# BUS.net
KiCad netlist of a schematic drawn in Altium Designer
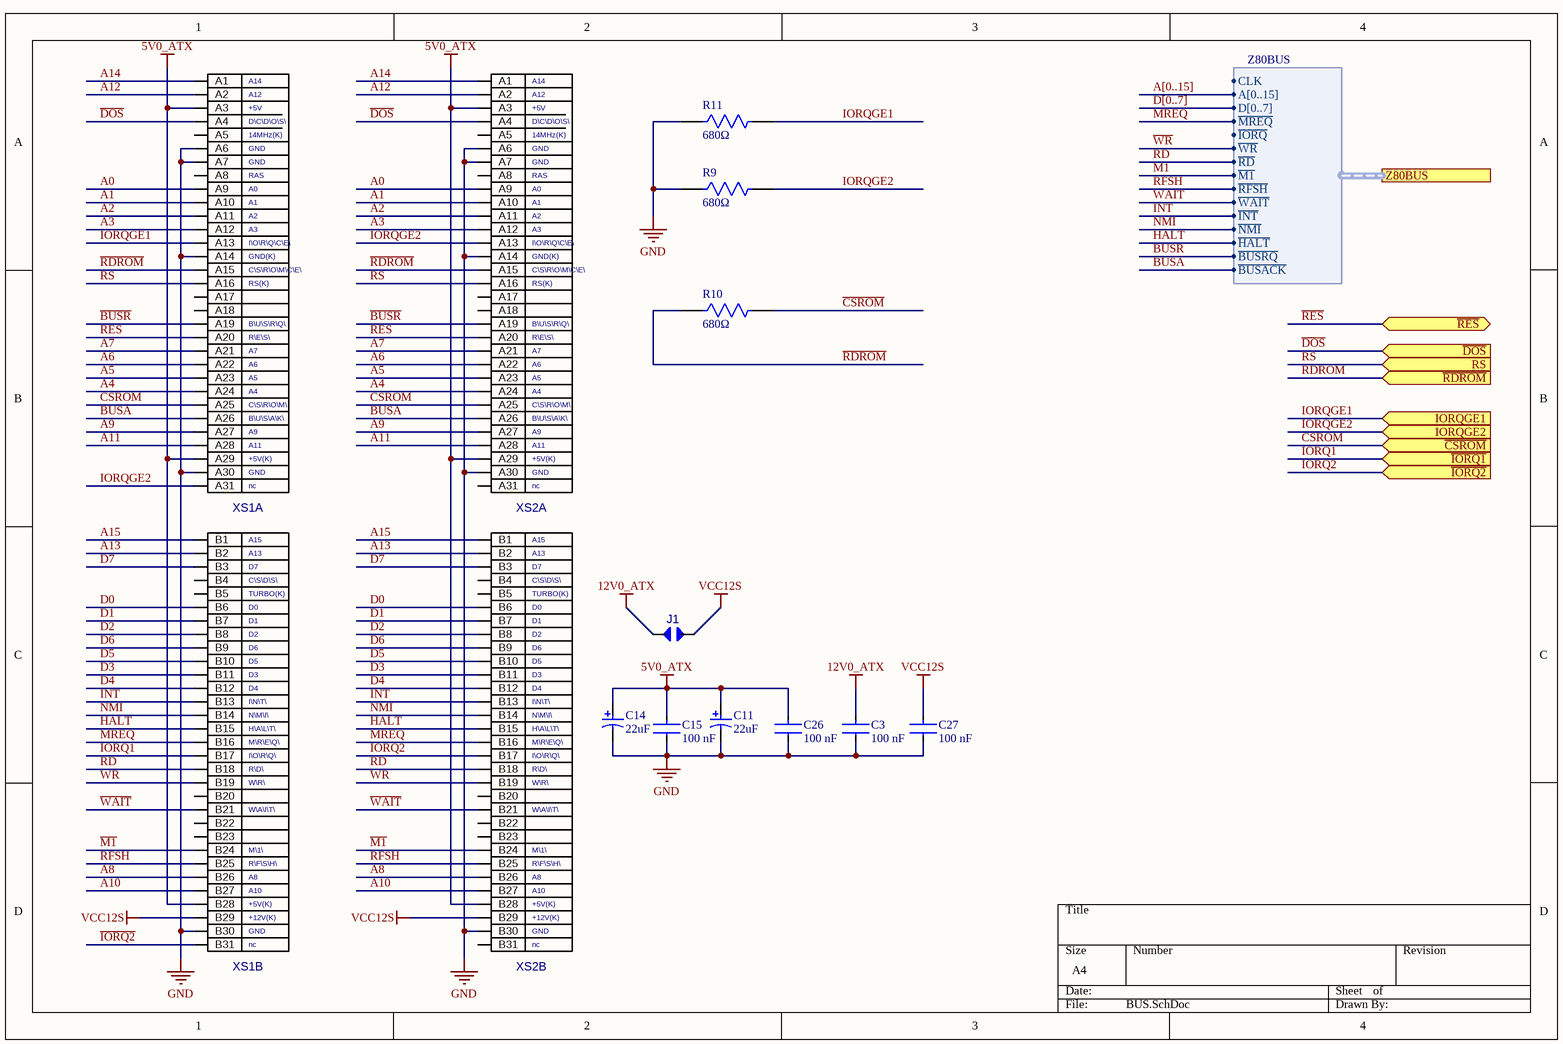
[diagram p0: BUS.SchDoc]

(export (version "E")
  (design (tool "Eeschema 10.0.6"))
  (components
    (comp (ref "C3")
      (value "CC0805KRX7R9BB104")
      (footprint "FP-CC0805-0_85-IPC_A")
      (description "CAP CER 0.1UF 50V X7R 0805")
      (fields (field (name "CAPACITANCE") "100 nF") (field (name "MANUFACTURER") "Yageo"))
      (libsource (lib "SchLib") (part "CMP-2100-03606-3"))
    )
    (comp (ref "C11")
      (value "TAJB226K016RNJ")
      (footprint "AVX-TAJ-B-2_M")
      (description "Standard Tantalum, 22 uF, +/- 10%, 16 V, -55 to 125 degC, 2-Pin SMD (1210), RoHS, Tape and Reel")
      (fields (field (name "CAPACITANCE") "22uF") (field (name "MANUFACTURER") "Kyocera AVX"))
      (libsource (lib "SchLib") (part "CMP-2100-03689-1"))
    )
    (comp (ref "C14")
      (value "TAJB226K016RNJ")
      (footprint "AVX-TAJ-B-2_M")
      (description "Standard Tantalum, 22 uF, +/- 10%, 16 V, -55 to 125 degC, 2-Pin SMD (1210), RoHS, Tape and Reel")
      (fields (field (name "CAPACITANCE") "22uF") (field (name "MANUFACTURER") "Kyocera AVX"))
      (libsource (lib "SchLib") (part "CMP-2100-03689-1"))
    )
    (comp (ref "C15")
      (value "CC0805KRX7R9BB104")
      (footprint "FP-CC0805-0_85-IPC_A")
      (description "CAP CER 0.1UF 50V X7R 0805")
      (fields (field (name "CAPACITANCE") "100 nF") (field (name "MANUFACTURER") "Yageo"))
      (libsource (lib "SchLib") (part "CMP-2100-03606-3"))
    )
    (comp (ref "C26")
      (value "CC0805KRX7R9BB104")
      (footprint "FP-CC0805-0_85-IPC_A")
      (description "CAP CER 0.1UF 50V X7R 0805")
      (fields (field (name "CAPACITANCE") "100 nF") (field (name "MANUFACTURER") "Yageo"))
      (libsource (lib "SchLib") (part "CMP-2100-03606-3"))
    )
    (comp (ref "C27")
      (value "CC0805KRX7R9BB104")
      (footprint "FP-CC0805-0_85-IPC_A")
      (description "CAP CER 0.1UF 50V X7R 0805")
      (fields (field (name "CAPACITANCE") "100 nF") (field (name "MANUFACTURER") "Yageo"))
      (libsource (lib "SchLib") (part "CMP-2100-03606-3"))
    )
    (comp (ref "J1")
      (value "JUMPER")
      (footprint "JUMPER_JUMPER(Primary)")
      (description "HLT->~IP")
      (libsource (lib "SchLib") (part "JUMPER"))
    )
    (comp (ref "R9")
      (value "680Ω")
      (footprint "FP-RT0805-IPC_A")
      (description "RES SMD 680 OHM 1% 1/8W 0805")
      (fields
        (field (name "MANUFACTURER") "Yageo")
        (field (name "MANUFACTURER PART NUMBER") "RT0805FRE07680RL")
      )
      (libsource (lib "SchLib") (part "CMP-03412-000082-1"))
    )
    (comp (ref "R10")
      (value "680Ω")
      (footprint "FP-RT0805-IPC_A")
      (description "RES SMD 680 OHM 1% 1/8W 0805")
      (fields
        (field (name "MANUFACTURER") "Yageo")
        (field (name "MANUFACTURER PART NUMBER") "RT0805FRE07680RL")
      )
      (libsource (lib "SchLib") (part "CMP-03412-000082-1"))
    )
    (comp (ref "R11")
      (value "680Ω")
      (footprint "FP-RT0805-IPC_A")
      (description "RES SMD 680 OHM 1% 1/8W 0805")
      (fields
        (field (name "MANUFACTURER") "Yageo")
        (field (name "MANUFACTURER PART NUMBER") "RT0805FRE07680RL")
      )
      (libsource (lib "SchLib") (part "CMP-03412-000082-1"))
    )
    (comp (ref "XS1")
      (value "ZXSLOT")
      (footprint "SLOT62_ZXSLOT(Primary)")
      (libsource (lib "SchLib") (part "ZXSLOT"))
    )
    (comp (ref "XS2")
      (value "ZXSLOT")
      (footprint "SLOT62_ZXSLOT(Primary)")
      (libsource (lib "SchLib") (part "ZXSLOT"))
    )
  )
  (nets
    (net (code "2") (name "/A0") (class "Default")
      (node (ref "XS1") (pin "A9") (pinfunction "A9_A9") (pintype "passive"))
      (node (ref "XS2") (pin "A9") (pinfunction "A9_A9") (pintype "passive"))
    )
    (net (code "3") (name "/A1") (class "Default")
      (node (ref "XS1") (pin "A10") (pinfunction "A10_A10") (pintype "passive"))
      (node (ref "XS2") (pin "A10") (pinfunction "A10_A10") (pintype "passive"))
    )
    (net (code "4") (name "/A2") (class "Default")
      (node (ref "XS1") (pin "A11") (pinfunction "A11_A11") (pintype "passive"))
      (node (ref "XS2") (pin "A11") (pinfunction "A11_A11") (pintype "passive"))
    )
    (net (code "5") (name "/A3") (class "Default")
      (node (ref "XS1") (pin "A12") (pinfunction "A12_A12") (pintype "passive"))
      (node (ref "XS2") (pin "A12") (pinfunction "A12_A12") (pintype "passive"))
    )
    (net (code "6") (name "/A4") (class "Default")
      (node (ref "XS1") (pin "A24") (pinfunction "A24_A24") (pintype "passive"))
      (node (ref "XS2") (pin "A24") (pinfunction "A24_A24") (pintype "passive"))
    )
    (net (code "7") (name "/A5") (class "Default")
      (node (ref "XS1") (pin "A23") (pinfunction "A23_A23") (pintype "passive"))
      (node (ref "XS2") (pin "A23") (pinfunction "A23_A23") (pintype "passive"))
    )
    (net (code "8") (name "/A6") (class "Default")
      (node (ref "XS1") (pin "A22") (pinfunction "A22_A22") (pintype "passive"))
      (node (ref "XS2") (pin "A22") (pinfunction "A22_A22") (pintype "passive"))
    )
    (net (code "9") (name "/A7") (class "Default")
      (node (ref "XS1") (pin "A21") (pinfunction "A21_A21") (pintype "passive"))
      (node (ref "XS2") (pin "A21") (pinfunction "A21_A21") (pintype "passive"))
    )
    (net (code "10") (name "/A8") (class "Default")
      (node (ref "XS1") (pin "B26") (pinfunction "B26_B26") (pintype "passive"))
      (node (ref "XS2") (pin "B26") (pinfunction "B26_B26") (pintype "passive"))
    )
    (net (code "11") (name "/A9") (class "Default")
      (node (ref "XS1") (pin "A27") (pinfunction "A27_A27") (pintype "passive"))
      (node (ref "XS2") (pin "A27") (pinfunction "A27_A27") (pintype "passive"))
    )
    (net (code "12") (name "/A10") (class "Default")
      (node (ref "XS1") (pin "B27") (pinfunction "B27_B27") (pintype "passive"))
      (node (ref "XS2") (pin "B27") (pinfunction "B27_B27") (pintype "passive"))
    )
    (net (code "13") (name "/A11") (class "Default")
      (node (ref "XS1") (pin "A28") (pinfunction "A28_A28") (pintype "passive"))
      (node (ref "XS2") (pin "A28") (pinfunction "A28_A28") (pintype "passive"))
    )
    (net (code "14") (name "/A12") (class "Default")
      (node (ref "XS1") (pin "A2") (pinfunction "A2_A2") (pintype "passive"))
      (node (ref "XS2") (pin "A2") (pinfunction "A2_A2") (pintype "passive"))
    )
    (net (code "15") (name "/A13") (class "Default")
      (node (ref "XS1") (pin "B2") (pinfunction "B2_B2") (pintype "passive"))
      (node (ref "XS2") (pin "B2") (pinfunction "B2_B2") (pintype "passive"))
    )
    (net (code "16") (name "/A14") (class "Default")
      (node (ref "XS1") (pin "A1") (pinfunction "A1_A1") (pintype "passive"))
      (node (ref "XS2") (pin "A1") (pinfunction "A1_A1") (pintype "passive"))
    )
    (net (code "17") (name "/A15") (class "Default")
      (node (ref "XS1") (pin "B1") (pinfunction "B1_B1") (pintype "passive"))
      (node (ref "XS2") (pin "B1") (pinfunction "B1_B1") (pintype "passive"))
    )
    (net (code "18") (name "/D0") (class "Default")
      (node (ref "XS1") (pin "B6") (pinfunction "B6_B6") (pintype "passive"))
      (node (ref "XS2") (pin "B6") (pinfunction "B6_B6") (pintype "passive"))
    )
    (net (code "19") (name "/D1") (class "Default")
      (node (ref "XS1") (pin "B7") (pinfunction "B7_B7") (pintype "passive"))
      (node (ref "XS2") (pin "B7") (pinfunction "B7_B7") (pintype "passive"))
    )
    (net (code "20") (name "/D2") (class "Default")
      (node (ref "XS1") (pin "B8") (pinfunction "B8_B8") (pintype "passive"))
      (node (ref "XS2") (pin "B8") (pinfunction "B8_B8") (pintype "passive"))
    )
    (net (code "21") (name "/D3") (class "Default")
      (node (ref "XS1") (pin "B11") (pinfunction "B11_B11") (pintype "passive"))
      (node (ref "XS2") (pin "B11") (pinfunction "B11_B11") (pintype "passive"))
    )
    (net (code "22") (name "/D4") (class "Default")
      (node (ref "XS1") (pin "B12") (pinfunction "B12_B12") (pintype "passive"))
      (node (ref "XS2") (pin "B12") (pinfunction "B12_B12") (pintype "passive"))
    )
    (net (code "23") (name "/D5") (class "Default")
      (node (ref "XS1") (pin "B10") (pinfunction "B10_B10") (pintype "passive"))
      (node (ref "XS2") (pin "B10") (pinfunction "B10_B10") (pintype "passive"))
    )
    (net (code "24") (name "/D6") (class "Default")
      (node (ref "XS1") (pin "B9") (pinfunction "B9_B9") (pintype "passive"))
      (node (ref "XS2") (pin "B9") (pinfunction "B9_B9") (pintype "passive"))
    )
    (net (code "25") (name "/D7") (class "Default")
      (node (ref "XS1") (pin "B3") (pinfunction "B3_B3") (pintype "passive"))
      (node (ref "XS2") (pin "B3") (pinfunction "B3_B3") (pintype "passive"))
    )
    (net (code "27") (name "/IORQGE1") (class "Default")
      (node (ref "R11") (pin "2") (pinfunction "2_2") (pintype "passive"))
      (node (ref "XS1") (pin "A13") (pinfunction "A13_A13") (pintype "passive"))
    )
    (net (code "28") (name "/IORQGE2") (class "Default")
      (node (ref "R9") (pin "2") (pinfunction "2_2") (pintype "passive"))
      (node (ref "XS1") (pin "A31") (pinfunction "A31_A31") (pintype "passive"))
      (node (ref "XS2") (pin "A13") (pinfunction "A13_A13") (pintype "passive"))
    )
    (net (code "29") (name "/RS") (class "Default")
      (node (ref "XS1") (pin "A16") (pinfunction "A16_A16") (pintype "passive"))
      (node (ref "XS2") (pin "A16") (pinfunction "A16_A16") (pintype "passive"))
    )
    (net (code "32") (name "/~{BUSA}") (class "Default")
      (node (ref "XS1") (pin "A26") (pinfunction "A26_A26") (pintype "passive"))
      (node (ref "XS2") (pin "A26") (pinfunction "A26_A26") (pintype "passive"))
    )
    (net (code "33") (name "/~{BUSR}") (class "Default")
      (node (ref "XS1") (pin "A19") (pinfunction "A19_A19") (pintype "passive"))
      (node (ref "XS2") (pin "A19") (pinfunction "A19_A19") (pintype "passive"))
    )
    (net (code "34") (name "/~{CSROM}") (class "Default")
      (node (ref "R10") (pin "2") (pinfunction "2_2") (pintype "passive"))
      (node (ref "XS1") (pin "A25") (pinfunction "A25_A25") (pintype "passive"))
      (node (ref "XS2") (pin "A25") (pinfunction "A25_A25") (pintype "passive"))
    )
    (net (code "35") (name "/~{DOS}") (class "Default")
      (node (ref "XS1") (pin "A4") (pinfunction "A4_A4") (pintype "passive"))
      (node (ref "XS2") (pin "A4") (pinfunction "A4_A4") (pintype "passive"))
    )
    (net (code "36") (name "/~{HALT}") (class "Default")
      (node (ref "XS1") (pin "B15") (pinfunction "B15_B15") (pintype "passive"))
      (node (ref "XS2") (pin "B15") (pinfunction "B15_B15") (pintype "passive"))
    )
    (net (code "37") (name "/~{INT}") (class "Default")
      (node (ref "XS1") (pin "B13") (pinfunction "B13_B13") (pintype "passive"))
      (node (ref "XS2") (pin "B13") (pinfunction "B13_B13") (pintype "passive"))
    )
    (net (code "38") (name "/~{IORQ1}") (class "Default")
      (node (ref "XS1") (pin "B17") (pinfunction "B17_B17") (pintype "passive"))
    )
    (net (code "39") (name "/~{IORQ2}") (class "Default")
      (node (ref "XS1") (pin "B31") (pinfunction "B31_B31") (pintype "passive"))
      (node (ref "XS2") (pin "B17") (pinfunction "B17_B17") (pintype "passive"))
    )
    (net (code "40") (name "/~{M1}") (class "Default")
      (node (ref "XS1") (pin "B24") (pinfunction "B24_B24") (pintype "passive"))
      (node (ref "XS2") (pin "B24") (pinfunction "B24_B24") (pintype "passive"))
    )
    (net (code "41") (name "/~{MREQ}") (class "Default")
      (node (ref "XS1") (pin "B16") (pinfunction "B16_B16") (pintype "passive"))
      (node (ref "XS2") (pin "B16") (pinfunction "B16_B16") (pintype "passive"))
    )
    (net (code "42") (name "/~{NMI}") (class "Default")
      (node (ref "XS1") (pin "B14") (pinfunction "B14_B14") (pintype "passive"))
      (node (ref "XS2") (pin "B14") (pinfunction "B14_B14") (pintype "passive"))
    )
    (net (code "43") (name "/~{RDROM}") (class "Default")
      (node (ref "R10") (pin "1") (pinfunction "1_1") (pintype "passive"))
      (node (ref "XS1") (pin "A15") (pinfunction "A15_A15") (pintype "passive"))
      (node (ref "XS2") (pin "A15") (pinfunction "A15_A15") (pintype "passive"))
    )
    (net (code "44") (name "/~{RD}") (class "Default")
      (node (ref "XS1") (pin "B18") (pinfunction "B18_B18") (pintype "passive"))
      (node (ref "XS2") (pin "B18") (pinfunction "B18_B18") (pintype "passive"))
    )
    (net (code "45") (name "/~{RES}") (class "Default")
      (node (ref "XS1") (pin "A20") (pinfunction "A20_A20") (pintype "passive"))
      (node (ref "XS2") (pin "A20") (pinfunction "A20_A20") (pintype "passive"))
    )
    (net (code "46") (name "/~{RFSH}") (class "Default")
      (node (ref "XS1") (pin "B25") (pinfunction "B25_B25") (pintype "passive"))
      (node (ref "XS2") (pin "B25") (pinfunction "B25_B25") (pintype "passive"))
    )
    (net (code "47") (name "/~{WAIT}") (class "Default")
      (node (ref "XS1") (pin "B21") (pinfunction "B21_B21") (pintype "passive"))
      (node (ref "XS2") (pin "B21") (pinfunction "B21_B21") (pintype "passive"))
    )
    (net (code "48") (name "/~{WR}") (class "Default")
      (node (ref "XS1") (pin "B19") (pinfunction "B19_B19") (pintype "passive"))
      (node (ref "XS2") (pin "B19") (pinfunction "B19_B19") (pintype "passive"))
    )
    (net (code "49") (name "5V0_ATX") (class "Default")
      (node (ref "C11") (pin "1") (pinfunction "1_1") (pintype "passive"))
      (node (ref "C14") (pin "1") (pinfunction "1_1") (pintype "passive"))
      (node (ref "C15") (pin "1") (pinfunction "1_1") (pintype "passive"))
      (node (ref "C26") (pin "1") (pinfunction "1_1") (pintype "passive"))
      (node (ref "XS1") (pin "A29") (pinfunction "A29_A29") (pintype "passive"))
      (node (ref "XS1") (pin "A3") (pinfunction "A3_A3") (pintype "passive"))
      (node (ref "XS1") (pin "B28") (pinfunction "B28_B28") (pintype "passive"))
      (node (ref "XS2") (pin "A29") (pinfunction "A29_A29") (pintype "passive"))
      (node (ref "XS2") (pin "A3") (pinfunction "A3_A3") (pintype "passive"))
      (node (ref "XS2") (pin "B28") (pinfunction "B28_B28") (pintype "passive"))
    )
    (net (code "50") (name "12V0_ATX") (class "Default")
      (node (ref "C3") (pin "1") (pinfunction "1_1") (pintype "passive"))
      (node (ref "J1") (pin "0") (pinfunction "1_0") (pintype "passive"))
    )
    (net (code "51") (name "GND") (class "Default")
      (node (ref "C11") (pin "2") (pinfunction "2_2") (pintype "passive"))
      (node (ref "C14") (pin "2") (pinfunction "2_2") (pintype "passive"))
      (node (ref "C15") (pin "2") (pinfunction "2_2") (pintype "passive"))
      (node (ref "C26") (pin "2") (pinfunction "2_2") (pintype "passive"))
      (node (ref "C27") (pin "2") (pinfunction "2_2") (pintype "passive"))
      (node (ref "C3") (pin "2") (pinfunction "2_2") (pintype "passive"))
      (node (ref "R11") (pin "1") (pinfunction "1_1") (pintype "passive"))
      (node (ref "R9") (pin "1") (pinfunction "1_1") (pintype "passive"))
      (node (ref "XS1") (pin "A14") (pinfunction "A14_A14") (pintype "passive"))
      (node (ref "XS1") (pin "A30") (pinfunction "A30_A30") (pintype "passive"))
      (node (ref "XS1") (pin "A6") (pinfunction "A6_A6") (pintype "passive"))
      (node (ref "XS1") (pin "A7") (pinfunction "A7_A7") (pintype "passive"))
      (node (ref "XS1") (pin "B30") (pinfunction "B30_B30") (pintype "passive"))
      (node (ref "XS2") (pin "A14") (pinfunction "A14_A14") (pintype "passive"))
      (node (ref "XS2") (pin "A30") (pinfunction "A30_A30") (pintype "passive"))
      (node (ref "XS2") (pin "A6") (pinfunction "A6_A6") (pintype "passive"))
      (node (ref "XS2") (pin "A7") (pinfunction "A7_A7") (pintype "passive"))
      (node (ref "XS2") (pin "B30") (pinfunction "B30_B30") (pintype "passive"))
    )
    (net (code "52") (name "VCC12S") (class "Default")
      (node (ref "C27") (pin "1") (pinfunction "1_1") (pintype "passive"))
      (node (ref "J1") (pin "1") (pinfunction "2_1") (pintype "passive"))
      (node (ref "XS1") (pin "B29") (pinfunction "B29_B29") (pintype "passive"))
      (node (ref "XS2") (pin "B29") (pinfunction "B29_B29") (pintype "passive"))
    )
    (net (code "53") (name "unconnected-(XS1-PadA5)") (class "Default")
      (node (ref "XS1") (pin "A5") (pinfunction "A5_A5") (pintype "passive"))
    )
    (net (code "54") (name "unconnected-(XS1-PadA8)") (class "Default")
      (node (ref "XS1") (pin "A8") (pinfunction "A8_A8") (pintype "passive"))
    )
    (net (code "55") (name "unconnected-(XS1-PadA17)") (class "Default")
      (node (ref "XS1") (pin "A17") (pinfunction "A17_A17") (pintype "passive"))
    )
    (net (code "56") (name "unconnected-(XS1-PadA18)") (class "Default")
      (node (ref "XS1") (pin "A18") (pinfunction "A18_A18") (pintype "passive"))
    )
    (net (code "57") (name "unconnected-(XS1-PadB4)") (class "Default")
      (node (ref "XS1") (pin "B4") (pinfunction "B4_B4") (pintype "passive"))
    )
    (net (code "58") (name "unconnected-(XS1-PadB5)") (class "Default")
      (node (ref "XS1") (pin "B5") (pinfunction "B5_B5") (pintype "passive"))
    )
    (net (code "59") (name "unconnected-(XS1-PadB20)") (class "Default")
      (node (ref "XS1") (pin "B20") (pinfunction "B20_B20") (pintype "passive"))
    )
    (net (code "60") (name "unconnected-(XS1-PadB22)") (class "Default")
      (node (ref "XS1") (pin "B22") (pinfunction "B22_B22") (pintype "passive"))
    )
    (net (code "61") (name "unconnected-(XS1-PadB23)") (class "Default")
      (node (ref "XS1") (pin "B23") (pinfunction "B23_B23") (pintype "passive"))
    )
    (net (code "62") (name "unconnected-(XS2-PadA5)") (class "Default")
      (node (ref "XS2") (pin "A5") (pinfunction "A5_A5") (pintype "passive"))
    )
    (net (code "63") (name "unconnected-(XS2-PadA8)") (class "Default")
      (node (ref "XS2") (pin "A8") (pinfunction "A8_A8") (pintype "passive"))
    )
    (net (code "64") (name "unconnected-(XS2-PadA17)") (class "Default")
      (node (ref "XS2") (pin "A17") (pinfunction "A17_A17") (pintype "passive"))
    )
    (net (code "65") (name "unconnected-(XS2-PadA18)") (class "Default")
      (node (ref "XS2") (pin "A18") (pinfunction "A18_A18") (pintype "passive"))
    )
    (net (code "66") (name "unconnected-(XS2-PadA31)") (class "Default")
      (node (ref "XS2") (pin "A31") (pinfunction "A31_A31") (pintype "passive"))
    )
    (net (code "67") (name "unconnected-(XS2-PadB4)") (class "Default")
      (node (ref "XS2") (pin "B4") (pinfunction "B4_B4") (pintype "passive"))
    )
    (net (code "68") (name "unconnected-(XS2-PadB5)") (class "Default")
      (node (ref "XS2") (pin "B5") (pinfunction "B5_B5") (pintype "passive"))
    )
    (net (code "69") (name "unconnected-(XS2-PadB20)") (class "Default")
      (node (ref "XS2") (pin "B20") (pinfunction "B20_B20") (pintype "passive"))
    )
    (net (code "70") (name "unconnected-(XS2-PadB22)") (class "Default")
      (node (ref "XS2") (pin "B22") (pinfunction "B22_B22") (pintype "passive"))
    )
    (net (code "71") (name "unconnected-(XS2-PadB23)") (class "Default")
      (node (ref "XS2") (pin "B23") (pinfunction "B23_B23") (pintype "passive"))
    )
    (net (code "72") (name "unconnected-(XS2-PadB31)") (class "Default")
      (node (ref "XS2") (pin "B31") (pinfunction "B31_B31") (pintype "passive"))
    )
  )
)
